# DAC.net
KiCad netlist of a schematic drawn in Altium Designer
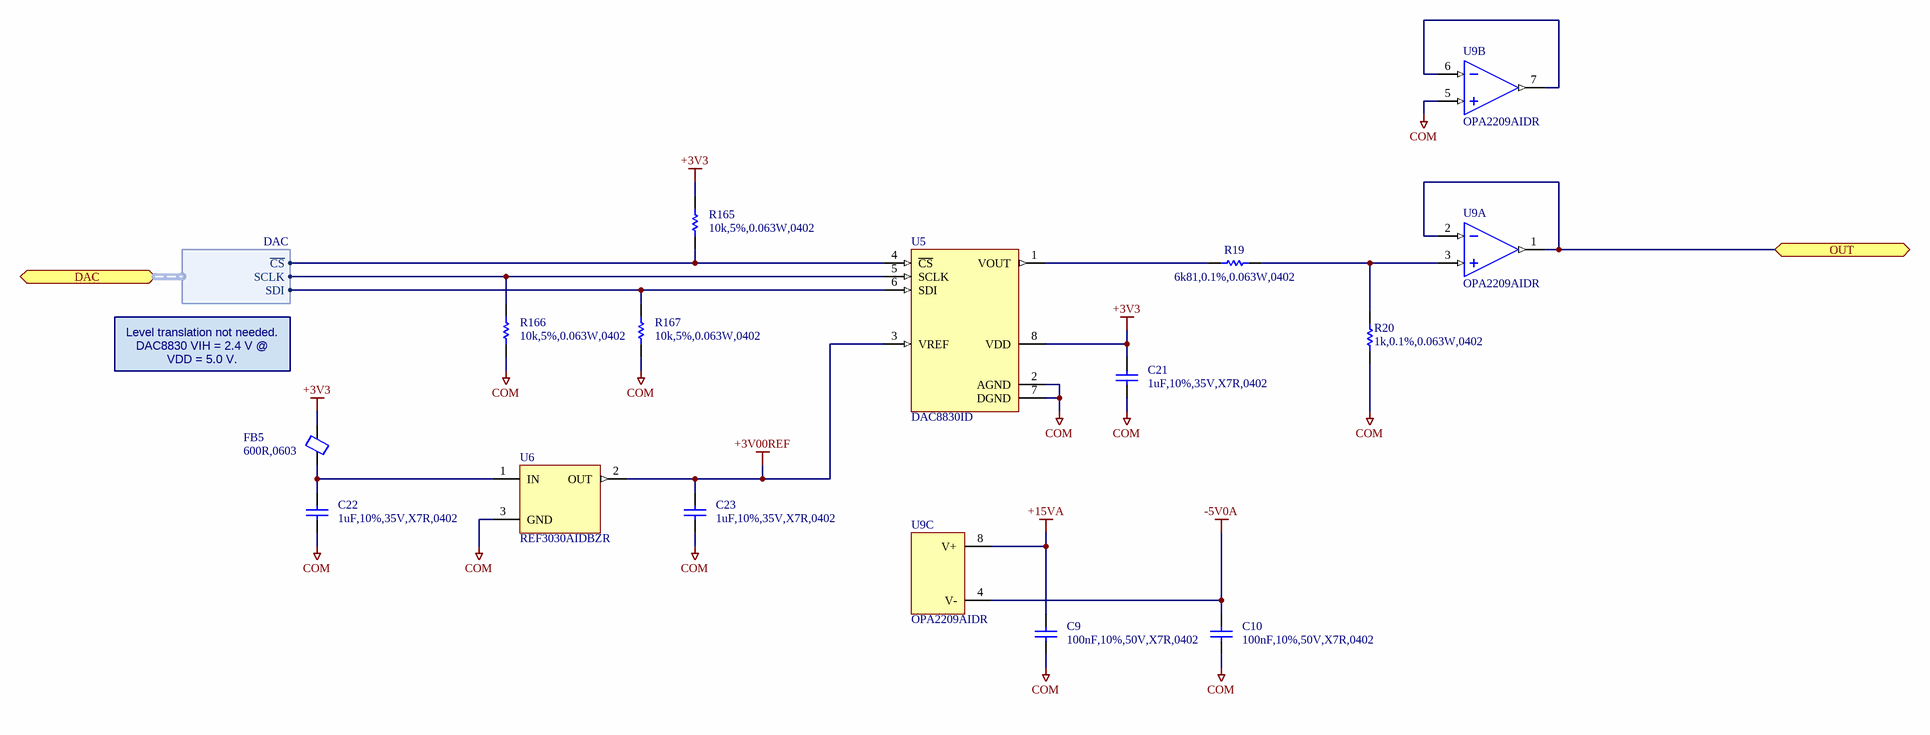
[diagram p0: DAC.SchDoc]

(export (version "E")
  (design (tool "Eeschema 10.0.6"))
  (components
    (comp (ref "C9")
      (value "100nF,10%,50V,X7R,0402")
      (footprint "CAPC1005X06N")
      (description "50V 100nF X7R Â±10% 0402 Ceramic Capacitors ROHS")
      (fields
        (field (name "MANUFACTURER 1 PART NUMBER") "GRM155R71H104KE14D")
        (field (name "VENDOR 1 PART NUMBER") "C77020")
        (field (name "CREATEDBY") "Judd Foster")
      )
      (libsource (lib "Component Library") (part "CAP,NPOL"))
    )
    (comp (ref "C10")
      (value "100nF,10%,50V,X7R,0402")
      (footprint "CAPC1005X06N")
      (description "50V 100nF X7R Â±10% 0402 Ceramic Capacitors ROHS")
      (fields
        (field (name "MANUFACTURER 1 PART NUMBER") "GRM155R71H104KE14D")
        (field (name "VENDOR 1 PART NUMBER") "C77020")
        (field (name "CREATEDBY") "Judd Foster")
      )
      (libsource (lib "Component Library") (part "CAP,NPOL"))
    )
    (comp (ref "C21")
      (value "1uF,10%,35V,X7R,0402")
      (footprint "CAPC1005X06N")
      (description "1 ï¿½F ï¿½10% 35V Ceramic Capacitor X5R 0402 (1005 Metric)")
      (fields
        (field (name "MANUFACTURER 1 PART NUMBER") "C1005X5R1V105K050BC")
        (field (name "VENDOR 1 PART NUMBER") "445-9073-1-ND")
        (field (name "CREATEDBY") "Judd Foster")
      )
      (libsource (lib "Component Library") (part "CAP,Cer,1uF,35VDC,X5R,0402"))
    )
    (comp (ref "C22")
      (value "1uF,10%,35V,X7R,0402")
      (footprint "CAPC1005X06N")
      (description "1 ï¿½F ï¿½10% 35V Ceramic Capacitor X5R 0402 (1005 Metric)")
      (fields
        (field (name "MANUFACTURER 1 PART NUMBER") "C1005X5R1V105K050BC")
        (field (name "VENDOR 1 PART NUMBER") "445-9073-1-ND")
        (field (name "CREATEDBY") "Judd Foster")
      )
      (libsource (lib "Component Library") (part "CAP,Cer,1uF,35VDC,X5R,0402"))
    )
    (comp (ref "C23")
      (value "1uF,10%,35V,X7R,0402")
      (footprint "CAPC1005X06N")
      (description "1 ï¿½F ï¿½10% 35V Ceramic Capacitor X5R 0402 (1005 Metric)")
      (fields
        (field (name "MANUFACTURER 1 PART NUMBER") "C1005X5R1V105K050BC")
        (field (name "VENDOR 1 PART NUMBER") "445-9073-1-ND")
        (field (name "CREATEDBY") "Judd Foster")
      )
      (libsource (lib "Component Library") (part "CAP,Cer,1uF,35VDC,X5R,0402"))
    )
    (comp (ref "FB5")
      (value "600R,0603")
      (footprint "INDC_0603")
      (description "500mÎ© Â±25% 600Î©@100MHz 0603 Ferrite Beads and Chips ROHS")
      (fields
        (field (name "MANUFACTURER 1 PART NUMBER") "FCM1608KF-601T03")
        (field (name "VENDOR 1 PART NUMBER") "C141723")
        (field (name "CREATEDBY") "Judd Foster")
      )
      (libsource (lib "Component Library") (part "FERRITE"))
    )
    (comp (ref "R19")
      (value "6k81,0.1%,0.063W,0402")
      (footprint "RESC1005X04N")
      (description "6.81kÎ© 62.5mW 50V Â±25ppm/â„ƒ Thin Film Resistor Â±0.1% 0402 Chip Resistor - Surface Mount RoHS")
      (fields
        (field (name "MANUFACTURER 1 PART NUMBER") "AT0402BRD076K81L")
        (field (name "VENDOR 1 PART NUMBER") "C851098")
        (field (name "CREATEDBY") "Judd Foster")
      )
      (libsource (lib "Component Library") (part "RES"))
    )
    (comp (ref "R20")
      (value "1k,0.1%,0.063W,0402")
      (footprint "RESC1005X04N")
      (description "1 kOhms Â±0.1% 0.063W, 1/16W Chip Resistor 0402 (1005 Metric) Thin Film")
      (fields
        (field (name "MANUFACTURER 1 PART NUMBER") "RT0402BRE071KL")
        (field (name "VENDOR 1 PART NUMBER") "YAG2306CT-ND")
        (field (name "CREATEDBY") "Judd Foster")
      )
      (libsource (lib "Component Library") (part "RES,1k,0.1%,0.063W,0402"))
    )
    (comp (ref "R165")
      (value "10k,5%,0.063W,0402")
      (footprint "RESC1005X04N")
      (description "10 kOhms ï¿½5% 0.063W, 1/16W Chip Resistor 0402 (1005 Metric) Automotive AEC-Q200 Thick Film")
      (fields
        (field (name "MANUFACTURER 1 PART NUMBER") "RMCF0402JT10K0")
        (field (name "VENDOR 1 PART NUMBER") "RMCF0402JT10K0CT-ND")
        (field (name "CREATEDBY") "Judd Foster")
      )
      (libsource (lib "Component Library") (part "RES,10k,5%,0.063W,0402"))
    )
    (comp (ref "R166")
      (value "10k,5%,0.063W,0402")
      (footprint "RESC1005X04N")
      (description "10 kOhms ï¿½5% 0.063W, 1/16W Chip Resistor 0402 (1005 Metric) Automotive AEC-Q200 Thick Film")
      (fields
        (field (name "MANUFACTURER 1 PART NUMBER") "RMCF0402JT10K0")
        (field (name "VENDOR 1 PART NUMBER") "RMCF0402JT10K0CT-ND")
        (field (name "CREATEDBY") "Judd Foster")
      )
      (libsource (lib "Component Library") (part "RES,10k,5%,0.063W,0402"))
    )
    (comp (ref "R167")
      (value "10k,5%,0.063W,0402")
      (footprint "RESC1005X04N")
      (description "10 kOhms ï¿½5% 0.063W, 1/16W Chip Resistor 0402 (1005 Metric) Automotive AEC-Q200 Thick Film")
      (fields
        (field (name "MANUFACTURER 1 PART NUMBER") "RMCF0402JT10K0")
        (field (name "VENDOR 1 PART NUMBER") "RMCF0402JT10K0CT-ND")
        (field (name "CREATEDBY") "Judd Foster")
      )
      (libsource (lib "Component Library") (part "RES,10k,5%,0.063W,0402"))
    )
    (comp (ref "U5")
      (value "DAC8830ID")
      (footprint "TEXASINSTRUMENTS_PKG_D0008A")
      (description "16 Bit Digital to Analog Converter 1 8-SOIC")
      (fields (field (name "VENDOR 1 PART NUMBER") "296-21738-5-ND") (field (name "CREATEDBY") "Judd Foster"))
      (libsource (lib "Component Library") (part "DAC8830ID"))
    )
    (comp (ref "U6")
      (value "REF3030AIDBZR")
      (footprint "SOT95P237X112-3N")
      (description "3V ï¿½0.2% 3.05V~5.5V 25mA Fixed SOT-23 Voltage References ROHS")
      (fields (field (name "VENDOR 1 PART NUMBER") "C38423") (field (name "CREATEDBY") "Judd Foster"))
      (libsource (lib "Component Library") (part "REF3030AIDBZR"))
    )
    (comp (ref "U9")
      (value "OPA2209AIDR")
      (footprint "TEXASINSTRUMENTS_PKG_D0008A")
      (description "35uV 18MHz 4.5nA 6.4V/us 130dB SOIC-8 Amplifiers ROHS")
      (fields (field (name "VENDOR 1 PART NUMBER") "C2057330") (field (name "CREATEDBY") "Judd Foster"))
      (libsource (lib "Component Library") (part "OPA2209AIDR"))
    )
  )
  (nets
    (net (code "2") (name "+3V00REF") (class "Default")
      (node (ref "C23") (pin "2") (pinfunction "2_2") (pintype "passive"))
      (node (ref "U5") (pin "3") (pinfunction "VREF_3") (pintype "input"))
      (node (ref "U6") (pin "2") (pinfunction "OUT_2") (pintype "output"))
    )
    (net (code "3") (name "+3V3") (class "Default")
      (node (ref "C21") (pin "2") (pinfunction "2_2") (pintype "passive"))
      (node (ref "FB5") (pin "2") (pinfunction "2_2") (pintype "passive"))
      (node (ref "R165") (pin "1") (pinfunction "1_1") (pintype "passive"))
      (node (ref "U5") (pin "8") (pinfunction "VDD_8") (pintype "power_in"))
    )
    (net (code "4") (name "+15VA") (class "Default")
      (node (ref "C9") (pin "2") (pinfunction "2_2") (pintype "passive"))
      (node (ref "U9") (pin "8") (pinfunction "V+_8") (pintype "power_in"))
    )
    (net (code "5") (name "-5V0A") (class "Default")
      (node (ref "C10") (pin "2") (pinfunction "2_2") (pintype "passive"))
      (node (ref "U9") (pin "4") (pinfunction "V-_4") (pintype "power_in"))
    )
    (net (code "6") (name "/OUT") (class "Default")
      (node (ref "U9") (pin "1") (pinfunction "OUTA_1") (pintype "output"))
      (node (ref "U9") (pin "2") (pinfunction "-INA_2") (pintype "input"))
    )
    (net (code "8") (name "COM") (class "Default")
      (node (ref "C10") (pin "1") (pinfunction "1_1") (pintype "passive"))
      (node (ref "C21") (pin "1") (pinfunction "1_1") (pintype "passive"))
      (node (ref "C22") (pin "1") (pinfunction "1_1") (pintype "passive"))
      (node (ref "C23") (pin "1") (pinfunction "1_1") (pintype "passive"))
      (node (ref "C9") (pin "1") (pinfunction "1_1") (pintype "passive"))
      (node (ref "R166") (pin "2") (pinfunction "2_2") (pintype "passive"))
      (node (ref "R167") (pin "2") (pinfunction "2_2") (pintype "passive"))
      (node (ref "R20") (pin "1") (pinfunction "1_1") (pintype "passive"))
      (node (ref "U5") (pin "2") (pinfunction "AGND_2") (pintype "power_in"))
      (node (ref "U5") (pin "7") (pinfunction "DGND_7") (pintype "power_in"))
      (node (ref "U6") (pin "3") (pinfunction "GND_3") (pintype "power_in"))
      (node (ref "U9") (pin "5") (pinfunction "+INB_5") (pintype "input"))
    )
    (net (code "9") (name "Net-(U5-SCLK)") (class "Default")
      (node (ref "R166") (pin "1") (pinfunction "1_1") (pintype "passive"))
      (node (ref "U5") (pin "5") (pinfunction "SCLK_5") (pintype "input"))
    )
    (net (code "10") (name "Net-(U5-SDI)") (class "Default")
      (node (ref "R167") (pin "1") (pinfunction "1_1") (pintype "passive"))
      (node (ref "U5") (pin "6") (pinfunction "SDI_6") (pintype "input"))
    )
    (net (code "11") (name "Net-(U5-VOUT)") (class "Default")
      (node (ref "R19") (pin "1") (pinfunction "1_1") (pintype "passive"))
      (node (ref "U5") (pin "1") (pinfunction "VOUT_1") (pintype "output"))
    )
    (net (code "12") (name "Net-(U5-~{CS})") (class "Default")
      (node (ref "R165") (pin "2") (pinfunction "2_2") (pintype "passive"))
      (node (ref "U5") (pin "4") (pinfunction "~{CS}_4") (pintype "input"))
    )
    (net (code "13") (name "Net-(U6-IN)") (class "Default")
      (node (ref "C22") (pin "2") (pinfunction "2_2") (pintype "passive"))
      (node (ref "FB5") (pin "1") (pinfunction "1_1") (pintype "passive"))
      (node (ref "U6") (pin "1") (pinfunction "IN_1") (pintype "power_in"))
    )
    (net (code "14") (name "Net-(U9A-+INA)") (class "Default")
      (node (ref "R19") (pin "2") (pinfunction "2_2") (pintype "passive"))
      (node (ref "R20") (pin "2") (pinfunction "2_2") (pintype "passive"))
      (node (ref "U9") (pin "3") (pinfunction "+INA_3") (pintype "input"))
    )
    (net (code "15") (name "Net-(U9B--INB)") (class "Default")
      (node (ref "U9") (pin "6") (pinfunction "-INB_6") (pintype "input"))
      (node (ref "U9") (pin "7") (pinfunction "OUTB_7") (pintype "output"))
    )
  )
)
